# PROC106B_RST_GPIOs_I2C.net
KiCad netlist of a schematic drawn in Altium Designer
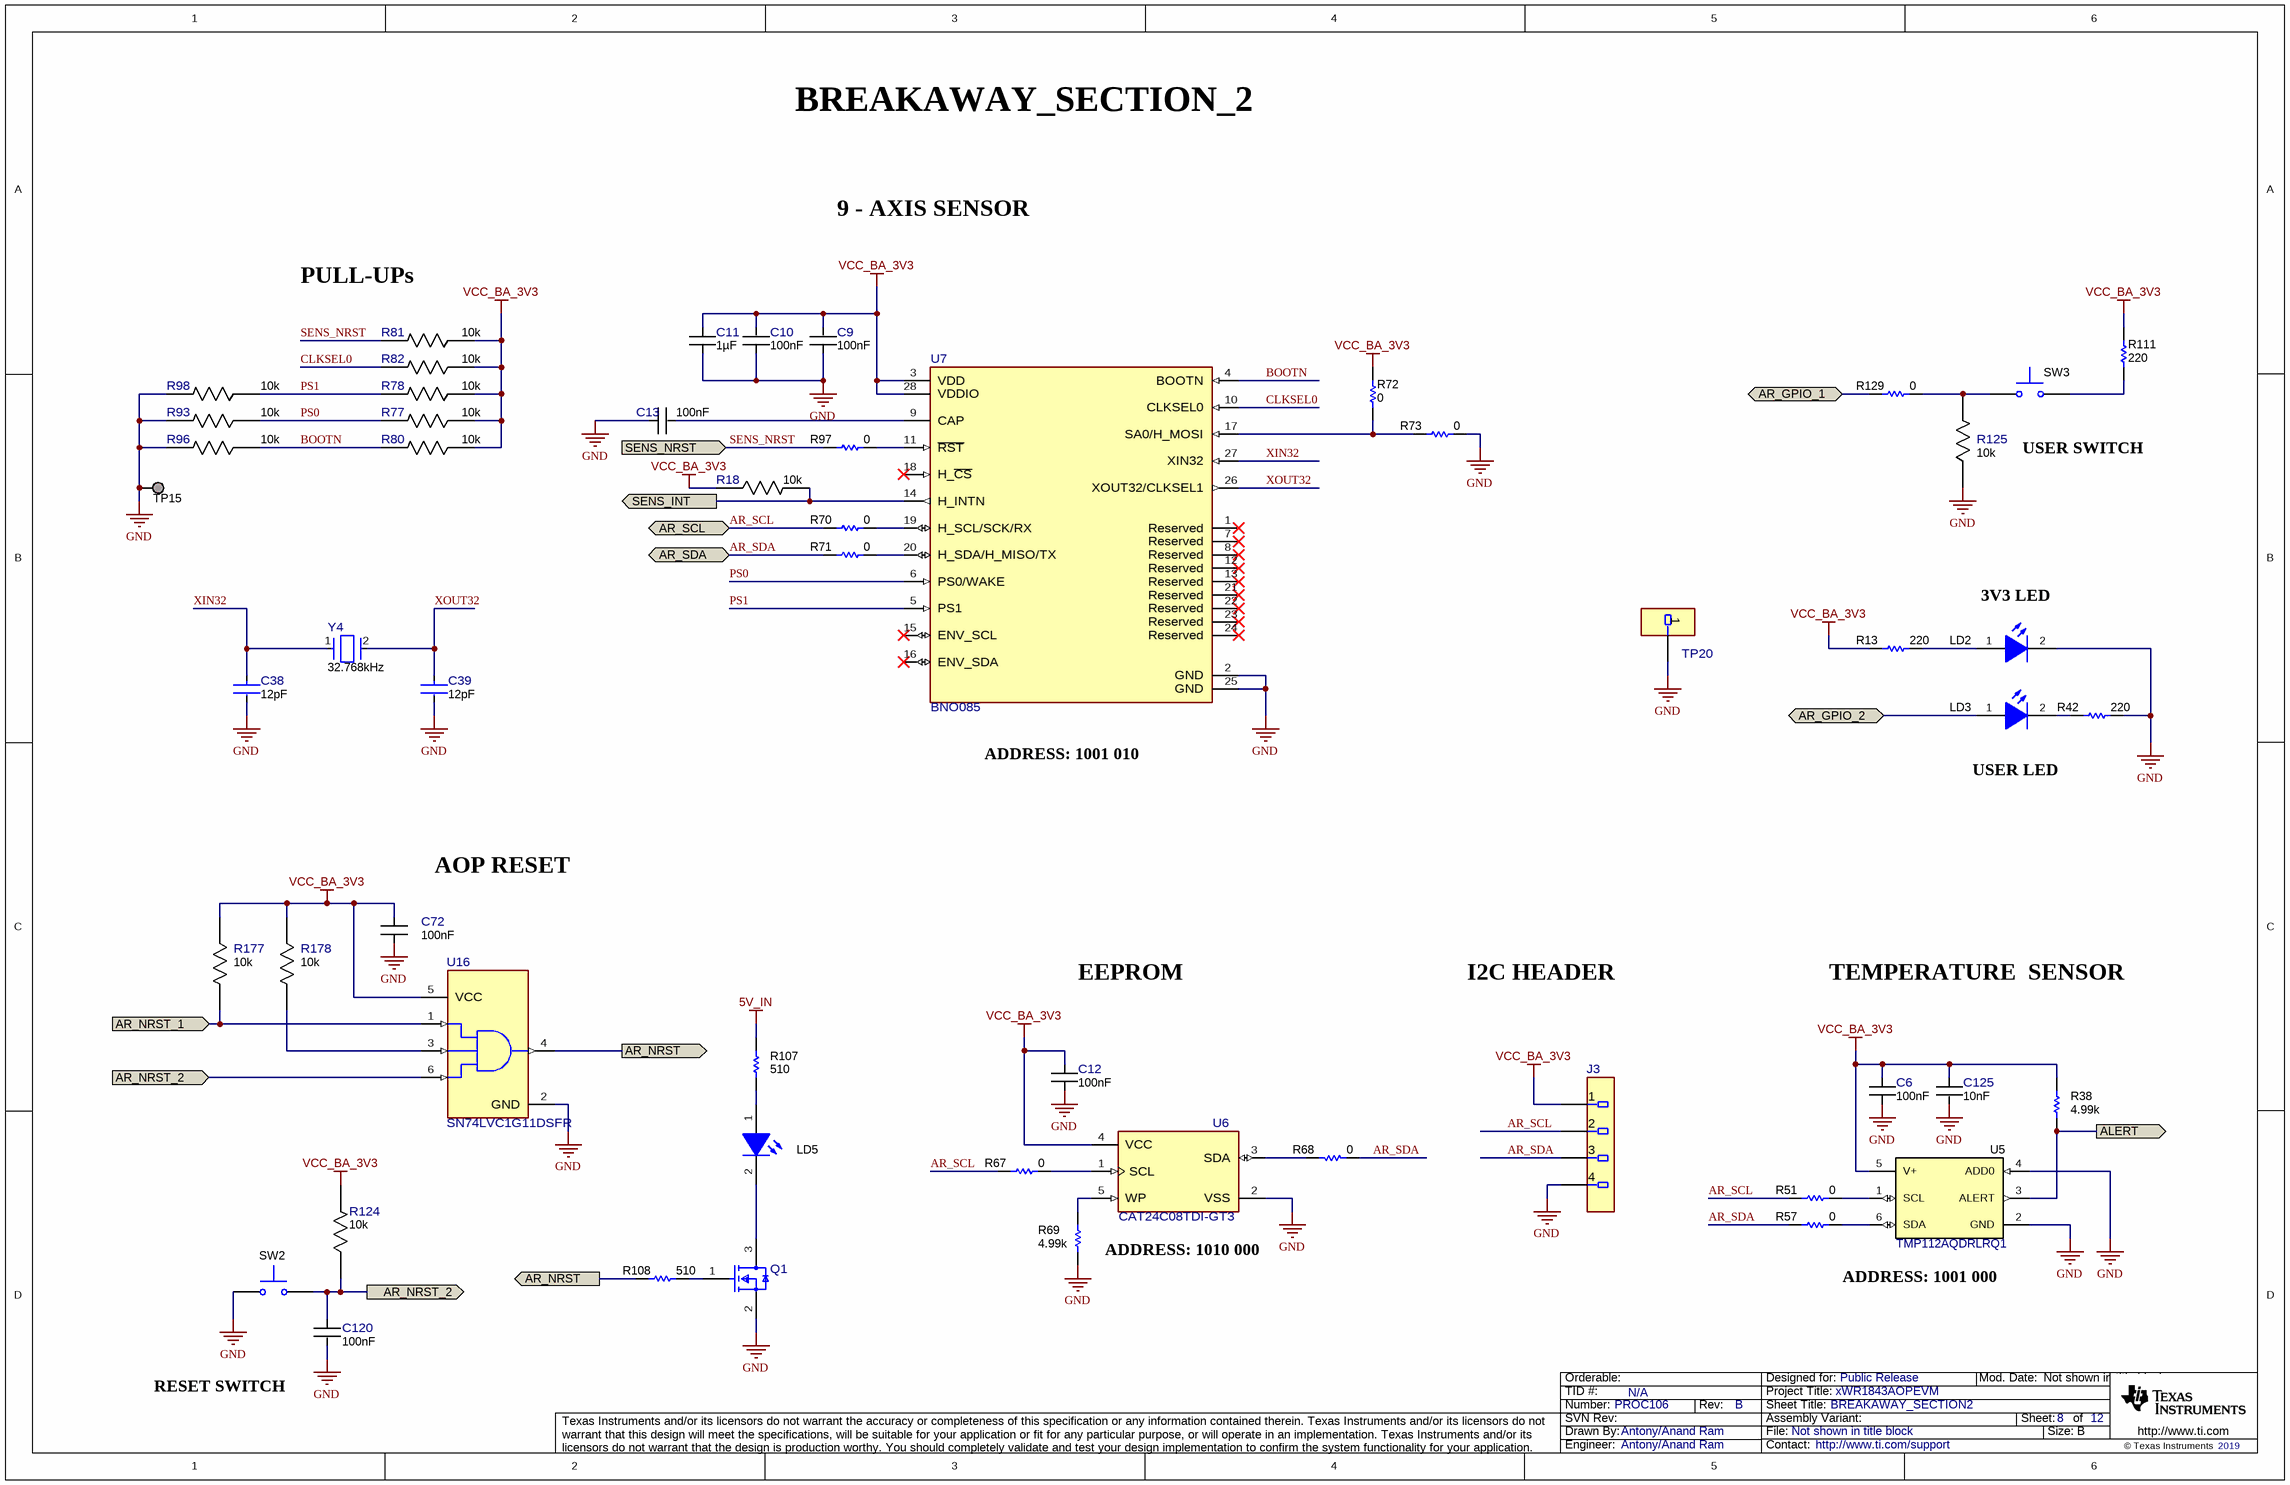
[diagram p0: PROC106B_RST_GPIOs_I2C.SchDoc]

(export (version "E")
  (design (tool "Eeschema 10.0.6"))
  (components
    (comp (ref "C6")
      (value "GRM033R6YA104KE14D")
      (footprint "FP-GRM033R6YA104KE14D_0201 (0603 Metric)-IPC_C")
      (description "Cap Ceramic 0.1uF 35V X5R 10% Pad SMD 0201 85C T/R")
      (fields (field (name "CAP_F") "100nF") (field (name "MANUFACTURER") "Murata Electronics North America"))
      (libsource (lib "Altium Vault - TI") (part "SYM-B32642B0223J"))
    )
    (comp (ref "C9")
      (value "GRM033R6YA104KE14D")
      (footprint "FP-GRM033R6YA104KE14D_0201 (0603 Metric)-IPC_C")
      (description "Cap Ceramic 0.1uF 35V X5R 10% Pad SMD 0201 85C T/R")
      (fields (field (name "CAP_F") "100nF") (field (name "MANUFACTURER") "Murata Electronics North America"))
      (libsource (lib "Altium Vault - TI") (part "SYM-B32642B0223J"))
    )
    (comp (ref "C10")
      (value "GRM033R6YA104KE14D")
      (footprint "FP-GRM033R6YA104KE14D_0201 (0603 Metric)-IPC_C")
      (description "Cap Ceramic 0.1uF 35V X5R 10% Pad SMD 0201 85C T/R")
      (fields (field (name "CAP_F") "100nF") (field (name "MANUFACTURER") "Murata Electronics North America"))
      (libsource (lib "Altium Vault - TI") (part "SYM-B32642B0223J"))
    )
    (comp (ref "C11")
      (value "CL03A105MO3NRNH")
      (footprint "FP-CL03A105MO3NRNH_0201-IPC_C")
      (description "1µF ±20% 16V Ceramic Capacitor X5R 0201")
      (fields (field (name "CAP_F") "1µF") (field (name "MANUFACTURER") "Samsung Electro-Mechanics"))
      (libsource (lib "Altium Vault - TI") (part "SYM-B32642B0223J"))
    )
    (comp (ref "C12")
      (value "GRM033R6YA104KE14D")
      (footprint "FP-GRM033R6YA104KE14D_0201 (0603 Metric)-IPC_C")
      (description "Cap Ceramic 0.1uF 35V X5R 10% Pad SMD 0201 85C T/R")
      (fields (field (name "CAP_F") "100nF") (field (name "MANUFACTURER") "Murata Electronics North America"))
      (libsource (lib "Altium Vault - TI") (part "SYM-B32642B0223J"))
    )
    (comp (ref "C13")
      (value "GRM033R6YA104KE14D")
      (footprint "FP-GRM033R6YA104KE14D_0201 (0603 Metric)-IPC_C")
      (description "Cap Ceramic 0.1uF 35V X5R 10% Pad SMD 0201 85C T/R")
      (fields (field (name "CAP_F") "100nF") (field (name "MANUFACTURER") "Murata Electronics North America"))
      (libsource (lib "Altium Vault - TI") (part "SYM-B32642B0223J"))
    )
    (comp (ref "C38")
      (value "250R05L120JV4T")
      (footprint "FP-250R05L120JV4T_0201-IPC_C")
      (description "CAP CER 12PF 25V C0G/NP0 0201")
      (fields (field (name "CAP_F") "12pF") (field (name "MANUFACTURER") "Johanson Technology Inc."))
      (libsource (lib "Altium Vault - TI") (part "SYM-CL31B335KAHVPNE"))
    )
    (comp (ref "C39")
      (value "250R05L120JV4T")
      (footprint "FP-250R05L120JV4T_0201-IPC_C")
      (description "CAP CER 12PF 25V C0G/NP0 0201")
      (fields (field (name "CAP_F") "12pF") (field (name "MANUFACTURER") "Johanson Technology Inc."))
      (libsource (lib "Altium Vault - TI") (part "SYM-CL31B335KAHVPNE"))
    )
    (comp (ref "C72")
      (value "GRM033R6YA104KE14D")
      (footprint "FP-GRM033R6YA104KE14D_0201 (0603 Metric)-IPC_C")
      (description "Cap Ceramic 0.1uF 35V X5R 10% Pad SMD 0201 85C T/R")
      (fields (field (name "CAP_F") "100nF") (field (name "MANUFACTURER") "Murata Electronics North America"))
      (libsource (lib "Altium Vault - TI") (part "SYM-B32642B0223J"))
    )
    (comp (ref "C120")
      (value "GRM033R6YA104KE14D")
      (footprint "FP-GRM033R6YA104KE14D_0201 (0603 Metric)-IPC_C")
      (description "Cap Ceramic 0.1uF 35V X5R 10% Pad SMD 0201 85C T/R")
      (fields (field (name "CAP_F") "100nF") (field (name "MANUFACTURER") "Murata Electronics North America"))
      (libsource (lib "Altium Vault - TI") (part "SYM-B32642B0223J"))
    )
    (comp (ref "C125")
      (value "CL03A103KA3NNNC")
      (footprint "FP-CL03A103KA3NNNC_0201-IPC_C")
      (description "CAP CER 10000PF 25V X5R 0201")
      (fields
        (field (name "CAP_F") "10nF")
        (field (name "MANUFACTURER") "Samsung Electro-Mechanics America, Inc")
      )
      (libsource (lib "Altium Vault - TI") (part "SYM-B32642B0223J"))
    )
    (comp (ref "J3")
      (value "M50-3930442")
      (footprint "FP-M50-3930442_HDR4-Recommended_Land_Pattern")
      (description "CONN HDR 1.27MM R/A AU 4POS")
      (fields (field (name "MANUFACTURER") "Harwin Inc."))
      (libsource (lib "Altium Vault - TI") (part "SYM-M50-3930442"))
    )
    (comp (ref "LD2")
      (value "APHHS1005CGCK")
      (footprint "APHHS1005_Green")
      (description "LED, Green, SMD")
      (fields (field (name "MANUFACTURER") "Kingbright"))
      (libsource (lib "Altium Vault - TI") (part "LED"))
    )
    (comp (ref "LD3")
      (value "APHHS1005CGCK")
      (footprint "APHHS1005_Green")
      (description "LED, Green, SMD")
      (fields (field (name "MANUFACTURER") "Kingbright"))
      (libsource (lib "Altium Vault - TI") (part "LED"))
    )
    (comp (ref "LD5")
      (value "APHHS1005CGCK")
      (footprint "APHHS1005_Green")
      (description "LED, Green, SMD")
      (fields (field (name "MANUFACTURER") "Kingbright"))
      (libsource (lib "Altium Vault - TI") (part "LED"))
    )
    (comp (ref "Q1")
      (value "BSS123-7-F")
      (footprint "FP-BSS123-7-F_SOT23-IPC_C")
      (description "MOSFET N-CH 100V 170MA SOT23-3")
      (fields (field (name "MANUFACTURER") "Diodes Incorporated"))
      (libsource (lib "Altium Vault - TI") (part "SYM-BSS123-7-F"))
    )
    (comp (ref "R13")
      (value "220")
      (footprint "0201L")
      (description "RES, 220, 5%, 0.05 W, 0201")
      (fields
        (field (name "MANUFACTURER") "Yageo America")
        (field (name "PARTNUMBER") "RC0201JR-07220RL")
        (field (name "PUBLISHER") "Texas Instruments")
      )
      (libsource (lib "Altium Vault - TI") (part "Resistor"))
    )
    (comp (ref "R18")
      (value "RR0306P-103-D")
      (footprint "FP-RR0306P-103-D_0201-IPC_C")
      (description "10 kOhms ±0.5% 0.05W, 1/20W Chip Resistor 0201 (0603 Metric)  Thin Film")
      (fields (field (name "MANUFACTURER") "Susumu") (field (name "RES_OHM") "10k"))
      (libsource (lib "Altium Vault - TI") (part "SYM-PMR18EZPJ000"))
    )
    (comp (ref "R38")
      (value "4.99k")
      (footprint "0201L")
      (description "RES, 4.99 k, 1%, 0.05 W, 0201")
      (fields
        (field (name "MANUFACTURER") "Yageo America")
        (field (name "PARTNUMBER") "RC0201FR-074K99L")
        (field (name "PUBLISHER") "Texas Instruments")
      )
      (libsource (lib "Altium Vault - TI") (part "Resistor"))
    )
    (comp (ref "R42")
      (value "220")
      (footprint "0201L")
      (description "RES, 220, 5%, 0.05 W, 0201")
      (fields
        (field (name "MANUFACTURER") "Yageo America")
        (field (name "PARTNUMBER") "RC0201JR-07220RL")
        (field (name "PUBLISHER") "Texas Instruments")
      )
      (libsource (lib "Altium Vault - TI") (part "Resistor"))
    )
    (comp (ref "R51")
      (value "RC0201JR-070RL")
      (footprint "FP-RC0201JR-070RL_0201 (0603 Metric)-MFG")
      (description "RES SMD 0 OHM JUMPER 1/20W 0201")
      (fields (field (name "MANUFACTURER") "Yageo") (field (name "RES_OHM") "0"))
      (libsource (lib "Altium Vault - TI") (part "SYM-WSR3R1500F"))
    )
    (comp (ref "R57")
      (value "RC0201JR-070RL")
      (footprint "FP-RC0201JR-070RL_0201 (0603 Metric)-MFG")
      (description "RES SMD 0 OHM JUMPER 1/20W 0201")
      (fields (field (name "MANUFACTURER") "Yageo") (field (name "RES_OHM") "0"))
      (libsource (lib "Altium Vault - TI") (part "SYM-WSR3R1500F"))
    )
    (comp (ref "R67")
      (value "RC0201JR-070RL")
      (footprint "FP-RC0201JR-070RL_0201 (0603 Metric)-MFG")
      (description "RES SMD 0 OHM JUMPER 1/20W 0201")
      (fields (field (name "MANUFACTURER") "Yageo") (field (name "RES_OHM") "0"))
      (libsource (lib "Altium Vault - TI") (part "SYM-WSR3R1500F"))
    )
    (comp (ref "R68")
      (value "RC0201JR-070RL")
      (footprint "FP-RC0201JR-070RL_0201 (0603 Metric)-MFG")
      (description "RES SMD 0 OHM JUMPER 1/20W 0201")
      (fields (field (name "MANUFACTURER") "Yageo") (field (name "RES_OHM") "0"))
      (libsource (lib "Altium Vault - TI") (part "SYM-WSR3R1500F"))
    )
    (comp (ref "R69")
      (value "4.99k")
      (footprint "0201L")
      (description "RES, 4.99 k, 1%, 0.05 W, 0201")
      (fields
        (field (name "MANUFACTURER") "Yageo America")
        (field (name "PARTNUMBER") "RC0201FR-074K99L")
        (field (name "PUBLISHER") "Texas Instruments")
      )
      (libsource (lib "Altium Vault - TI") (part "Resistor"))
    )
    (comp (ref "R70")
      (value "RC0201JR-070RL")
      (footprint "FP-RC0201JR-070RL_0201 (0603 Metric)-MFG")
      (description "RES SMD 0 OHM JUMPER 1/20W 0201")
      (fields (field (name "MANUFACTURER") "Yageo") (field (name "RES_OHM") "0"))
      (libsource (lib "Altium Vault - TI") (part "SYM-WSR3R1500F"))
    )
    (comp (ref "R71")
      (value "RC0201JR-070RL")
      (footprint "FP-RC0201JR-070RL_0201 (0603 Metric)-MFG")
      (description "RES SMD 0 OHM JUMPER 1/20W 0201")
      (fields (field (name "MANUFACTURER") "Yageo") (field (name "RES_OHM") "0"))
      (libsource (lib "Altium Vault - TI") (part "SYM-WSR3R1500F"))
    )
    (comp (ref "R72")
      (value "RC0201JR-070RL")
      (footprint "FP-RC0201JR-070RL_0201 (0603 Metric)-IPC_C")
      (description "RES SMD 0 OHM JUMPER 1/20W 0201")
      (fields (field (name "MANUFACTURER") "Yageo") (field (name "RES_OHM") "0"))
      (libsource (lib "Altium Vault - TI") (part "SYM-WSR3R1500F"))
    )
    (comp (ref "R73")
      (value "RC0201JR-070RL")
      (footprint "FP-RC0201JR-070RL_0201 (0603 Metric)-IPC_C")
      (description "RES SMD 0 OHM JUMPER 1/20W 0201")
      (fields (field (name "MANUFACTURER") "Yageo") (field (name "RES_OHM") "0"))
      (libsource (lib "Altium Vault - TI") (part "SYM-WSR3R1500F"))
    )
    (comp (ref "R77")
      (value "RR0306P-103-D")
      (footprint "FP-RR0306P-103-D_0201-IPC_C")
      (description "10 kOhms ±0.5% 0.05W, 1/20W Chip Resistor 0201 (0603 Metric)  Thin Film")
      (fields (field (name "MANUFACTURER") "Susumu") (field (name "RES_OHM") "10k"))
      (libsource (lib "Altium Vault - TI") (part "SYM-PMR18EZPJ000"))
    )
    (comp (ref "R78")
      (value "RR0306P-103-D")
      (footprint "FP-RR0306P-103-D_0201-IPC_C")
      (description "10 kOhms ±0.5% 0.05W, 1/20W Chip Resistor 0201 (0603 Metric)  Thin Film")
      (fields (field (name "MANUFACTURER") "Susumu") (field (name "RES_OHM") "10k"))
      (libsource (lib "Altium Vault - TI") (part "SYM-PMR18EZPJ000"))
    )
    (comp (ref "R80")
      (value "RR0306P-103-D")
      (footprint "FP-RR0306P-103-D_0201-IPC_C")
      (description "10 kOhms ±0.5% 0.05W, 1/20W Chip Resistor 0201 (0603 Metric)  Thin Film")
      (fields (field (name "MANUFACTURER") "Susumu") (field (name "RES_OHM") "10k"))
      (libsource (lib "Altium Vault - TI") (part "SYM-PMR18EZPJ000"))
    )
    (comp (ref "R81")
      (value "RR0306P-103-D")
      (footprint "FP-RR0306P-103-D_0201-IPC_C")
      (description "10 kOhms ±0.5% 0.05W, 1/20W Chip Resistor 0201 (0603 Metric)  Thin Film")
      (fields (field (name "MANUFACTURER") "Susumu") (field (name "RES_OHM") "10k"))
      (libsource (lib "Altium Vault - TI") (part "SYM-PMR18EZPJ000"))
    )
    (comp (ref "R82")
      (value "RR0306P-103-D")
      (footprint "FP-RR0306P-103-D_0201-IPC_C")
      (description "10 kOhms ±0.5% 0.05W, 1/20W Chip Resistor 0201 (0603 Metric)  Thin Film")
      (fields (field (name "MANUFACTURER") "Susumu") (field (name "RES_OHM") "10k"))
      (libsource (lib "Altium Vault - TI") (part "SYM-PMR18EZPJ000"))
    )
    (comp (ref "R93")
      (value "RR0306P-103-D")
      (footprint "FP-RR0306P-103-D_0201-IPC_C")
      (description "10 kOhms ±0.5% 0.05W, 1/20W Chip Resistor 0201 (0603 Metric)  Thin Film")
      (fields (field (name "MANUFACTURER") "Susumu") (field (name "RES_OHM") "10k"))
      (libsource (lib "Altium Vault - TI") (part "SYM-PMR18EZPJ000"))
    )
    (comp (ref "R96")
      (value "RR0306P-103-D")
      (footprint "FP-RR0306P-103-D_0201-IPC_C")
      (description "10 kOhms ±0.5% 0.05W, 1/20W Chip Resistor 0201 (0603 Metric)  Thin Film")
      (fields (field (name "MANUFACTURER") "Susumu") (field (name "RES_OHM") "10k"))
      (libsource (lib "Altium Vault - TI") (part "SYM-PMR18EZPJ000"))
    )
    (comp (ref "R97")
      (value "RC0201JR-070RL")
      (footprint "FP-RC0201JR-070RL_0201 (0603 Metric)-IPC_C")
      (description "RES SMD 0 OHM JUMPER 1/20W 0201")
      (fields (field (name "MANUFACTURER") "Yageo") (field (name "RES_OHM") "0"))
      (libsource (lib "Altium Vault - TI") (part "SYM-WSR3R1500F"))
    )
    (comp (ref "R98")
      (value "RR0306P-103-D")
      (footprint "FP-RR0306P-103-D_0201-IPC_C")
      (description "10 kOhms ±0.5% 0.05W, 1/20W Chip Resistor 0201 (0603 Metric)  Thin Film")
      (fields (field (name "MANUFACTURER") "Susumu") (field (name "RES_OHM") "10k"))
      (libsource (lib "Altium Vault - TI") (part "SYM-PMR18EZPJ000"))
    )
    (comp (ref "R107")
      (value "510")
      (footprint "0201L")
      (description "RES, 510, 5%, 0.05 W, 0201")
      (fields
        (field (name "MANUFACTURER") "Yageo America")
        (field (name "PARTNUMBER") "RC0201JR-07510RL")
        (field (name "PUBLISHER") "Texas Instruments")
      )
      (libsource (lib "Altium Vault - TI") (part "Resistor"))
    )
    (comp (ref "R108")
      (value "510")
      (footprint "0201L")
      (description "RES, 510, 5%, 0.05 W, 0201")
      (fields
        (field (name "MANUFACTURER") "Yageo America")
        (field (name "PARTNUMBER") "RC0201JR-07510RL")
        (field (name "PUBLISHER") "Texas Instruments")
      )
      (libsource (lib "Altium Vault - TI") (part "Resistor"))
    )
    (comp (ref "R111")
      (value "220")
      (footprint "0201L")
      (description "RES, 220, 5%, 0.05 W, 0201")
      (fields
        (field (name "MANUFACTURER") "Yageo America")
        (field (name "PARTNUMBER") "RC0201JR-07220RL")
        (field (name "PUBLISHER") "Texas Instruments")
      )
      (libsource (lib "Altium Vault - TI") (part "Resistor"))
    )
    (comp (ref "R124")
      (value "RR0306P-103-D")
      (footprint "FP-RR0306P-103-D_0201-IPC_C")
      (description "10 kOhms ±0.5% 0.05W, 1/20W Chip Resistor 0201 (0603 Metric)  Thin Film")
      (fields (field (name "MANUFACTURER") "Susumu") (field (name "RES_OHM") "10k"))
      (libsource (lib "Altium Vault - TI") (part "SYM-PMR18EZPJ000"))
    )
    (comp (ref "R125")
      (value "RR0306P-103-D")
      (footprint "FP-RR0306P-103-D_0201-IPC_C")
      (description "10 kOhms ±0.5% 0.05W, 1/20W Chip Resistor 0201 (0603 Metric)  Thin Film")
      (fields (field (name "MANUFACTURER") "Susumu") (field (name "RES_OHM") "10k"))
      (libsource (lib "Altium Vault - TI") (part "SYM-PMR18EZPJ000"))
    )
    (comp (ref "R129")
      (value "RC0201JR-070RL")
      (footprint "FP-RC0201JR-070RL_0201 (0603 Metric)-IPC_C")
      (description "RES SMD 0 OHM JUMPER 1/20W 0201")
      (fields (field (name "MANUFACTURER") "Yageo") (field (name "RES_OHM") "0"))
      (libsource (lib "Altium Vault - TI") (part "SYM-WSR3R1500F"))
    )
    (comp (ref "R177")
      (value "RR0306P-103-D")
      (footprint "FP-RR0306P-103-D_0201-IPC_C")
      (description "10 kOhms ±0.5% 0.05W, 1/20W Chip Resistor 0201 (0603 Metric)  Thin Film")
      (fields (field (name "MANUFACTURER") "Susumu") (field (name "RES_OHM") "10k"))
      (libsource (lib "Altium Vault - TI") (part "SYM-PMR18EZPJ000"))
    )
    (comp (ref "R178")
      (value "RR0306P-103-D")
      (footprint "FP-RR0306P-103-D_0201-IPC_C")
      (description "10 kOhms ±0.5% 0.05W, 1/20W Chip Resistor 0201 (0603 Metric)  Thin Film")
      (fields (field (name "MANUFACTURER") "Susumu") (field (name "RES_OHM") "10k"))
      (libsource (lib "Altium Vault - TI") (part "SYM-PMR18EZPJ000"))
    )
    (comp (ref "SW2")
      (value "B3U-1000P")
      (footprint "SW_B3U-1000P")
      (description "SWITCH TACTILE SPST-NO 0.05A 12V")
      (fields
        (field (name "MANUFACTURER") "Omron Electronic Components")
        (field (name "PUBLISHER") "Texas Instruments")
      )
      (libsource (lib "Altium Vault - TI") (part "Switch_PushButton"))
    )
    (comp (ref "SW3")
      (value "B3U-1000P")
      (footprint "SW_B3U-1000P")
      (description "SWITCH TACTILE SPST-NO 0.05A 12V")
      (fields
        (field (name "MANUFACTURER") "Omron Electronic Components")
        (field (name "PUBLISHER") "Texas Instruments")
      )
      (libsource (lib "Altium Vault - TI") (part "Switch_PushButton"))
    )
    (comp (ref "TP15")
      (value "TESTPOINT")
      (footprint "TP_25MIL-SMT")
      (description "TEST POINT.  No entry in BOM.")
      (libsource (lib "Altium Vault - TI") (part "TESTPOINT"))
    )
    (comp (ref "TP20")
      (value "4953")
      (footprint "FP-4953_HDR1-MFG")
      (description "PC Test Point, Loop Brass, Tin Plating 0.047\" (1.19mm) Hole Diameter Mounting Type")
      (fields (field (name "MANUFACTURER") "Keystone Electronics"))
      (libsource (lib "Altium Vault - TI") (part "SYM-4953"))
    )
    (comp (ref "U5")
      (value "TMP112AQDRLRQ1")
      (footprint "DRL0006A")
      (fields
        (field (name "MANUFACTURER") "Texas Instruments")
        (field (name "PUBLISHER") "Texas Instruments")
      )
      (libsource (lib "Altium Vault - TI") (part "TMP112"))
    )
    (comp (ref "U6")
      (value "CAT24C08TDI-GT3")
      (footprint "FP-CAT24C08TDI-GT3_TSOT-23-5-IPC_A")
      (description "8KB I2C SER EEPROM TSOT 23")
      (fields (field (name "MANUFACTURER") "ON Semiconductor"))
      (libsource (lib "Altium Vault - TI") (part "SYM-CAT24C08TDI-GT3"))
    )
    (comp (ref "U7")
      (value "BNO085")
      (footprint "FP-BNO085_LGA28-MFG")
      (description "IMU ACCEL/GYRO/MAG I2C 32BIT")
      (fields (field (name "MANUFACTURER") "Hillcrest Laboratories, Inc."))
      (libsource (lib "Altium Vault - TI") (part "SYM-BNO085"))
    )
    (comp (ref "U16")
      (value "SN74LVC1G11DSFR")
      (footprint "DSF0006A-MFG")
      (description "AND Gate IC 1 Channel  6-SON (1x1)")
      (fields
        (field (name "MOUSER PART NUMBER") "595-SN74LVC1G11DSFR")
        (field (name "DIGIKEY PART NUMBER") "296-30121-1-ND")
      )
      (libsource (lib "Altium Vault - TI") (part "SYM-SN74LVC1G11DSFR"))
    )
    (comp (ref "Y4")
      (value "ABS05W-32.768KHZ-D-2-T")
      (footprint "FP-ABS05W-32.768KHZ-D-2-T_XTAL_SMT_1MM6_1MM0-MFG")
      (description "CRYSTAL 32.768KHZ 4PF SMD")
      (fields (field (name "FREQUENCY_FIXED") "32.768kHz") (field (name "MANUFACTURER") "Abracon LLC"))
      (libsource (lib "Altium Vault - TI") (part "SYM-ABS05W-32.768KHZ-D-2-T"))
    )
  )
  (nets
    (net (code "1") (name "/ALERT") (class "Default")
      (node (ref "R38") (pin "1") (pinfunction "1_1") (pintype "passive"))
      (node (ref "U5") (pin "3") (pinfunction "ALERT_3") (pintype "output"))
    )
    (net (code "2") (name "/AR_GPIO_1") (class "Default")
      (node (ref "R129") (pin "2") (pinfunction "2_2") (pintype "passive"))
    )
    (net (code "3") (name "/AR_GPIO_2") (class "Default")
      (node (ref "LD3") (pin "1") (pinfunction "A_1") (pintype "passive"))
    )
    (net (code "4") (name "/AR_NRST") (class "Default")
      (node (ref "R108") (pin "1") (pinfunction "1_1") (pintype "passive"))
      (node (ref "U16") (pin "4") (pinfunction "Y_4") (pintype "output"))
    )
    (net (code "5") (name "/AR_NRST_1") (class "Default")
      (node (ref "R177") (pin "2") (pinfunction "2_2") (pintype "passive"))
      (node (ref "U16") (pin "1") (pinfunction "A_1") (pintype "input"))
    )
    (net (code "6") (name "/AR_NRST_2") (class "Default")
      (node (ref "C120") (pin "1") (pinfunction "1_1") (pintype "passive"))
      (node (ref "R124") (pin "1") (pinfunction "1_1") (pintype "passive"))
      (node (ref "SW2") (pin "1") (pinfunction "1_1") (pintype "passive"))
      (node (ref "U16") (pin "6") (pinfunction "C_6") (pintype "input"))
    )
    (net (code "7") (name "/AR_SCL") (class "Default")
      (node (ref "J3") (pin "2") (pinfunction "2_2") (pintype "passive"))
      (node (ref "R51") (pin "1") (pinfunction "1_1") (pintype "passive"))
      (node (ref "R67") (pin "1") (pinfunction "1_1") (pintype "passive"))
      (node (ref "R70") (pin "2") (pinfunction "2_2") (pintype "passive"))
    )
    (net (code "8") (name "/AR_SDA") (class "Default")
      (node (ref "J3") (pin "3") (pinfunction "3_3") (pintype "passive"))
      (node (ref "R57") (pin "1") (pinfunction "1_1") (pintype "passive"))
      (node (ref "R68") (pin "1") (pinfunction "1_1") (pintype "passive"))
      (node (ref "R71") (pin "2") (pinfunction "2_2") (pintype "passive"))
    )
    (net (code "9") (name "/BOOTN") (class "Default")
      (node (ref "R80") (pin "2") (pinfunction "2_2") (pintype "passive"))
      (node (ref "R96") (pin "1") (pinfunction "1_1") (pintype "passive"))
      (node (ref "U7") (pin "4") (pinfunction "BOOTN_4") (pintype "input"))
    )
    (net (code "10") (name "/CLKSEL0") (class "Default")
      (node (ref "R82") (pin "2") (pinfunction "2_2") (pintype "passive"))
      (node (ref "U7") (pin "10") (pinfunction "CLKSEL0_10") (pintype "input"))
    )
    (net (code "11") (name "/PS0") (class "Default")
      (node (ref "R77") (pin "2") (pinfunction "2_2") (pintype "passive"))
      (node (ref "R93") (pin "1") (pinfunction "1_1") (pintype "passive"))
      (node (ref "U7") (pin "6") (pinfunction "PS0/WAKE_6") (pintype "input"))
    )
    (net (code "12") (name "/PS1") (class "Default")
      (node (ref "R78") (pin "2") (pinfunction "2_2") (pintype "passive"))
      (node (ref "R98") (pin "1") (pinfunction "1_1") (pintype "passive"))
      (node (ref "U7") (pin "5") (pinfunction "PS1_5") (pintype "input"))
    )
    (net (code "13") (name "/SENS_INT") (class "Default")
      (node (ref "R18") (pin "2") (pinfunction "2_2") (pintype "passive"))
      (node (ref "U7") (pin "14") (pinfunction "H_INTN_14") (pintype "output"))
    )
    (net (code "14") (name "/SENS_NRST") (class "Default")
      (node (ref "R81") (pin "2") (pinfunction "2_2") (pintype "passive"))
      (node (ref "R97") (pin "2") (pinfunction "2_2") (pintype "passive"))
    )
    (net (code "15") (name "/XIN32") (class "Default")
      (node (ref "C38") (pin "1") (pinfunction "1_1") (pintype "passive"))
      (node (ref "U7") (pin "27") (pinfunction "XIN32_27") (pintype "input"))
      (node (ref "Y4") (pin "1") (pinfunction "1_1") (pintype "passive"))
    )
    (net (code "16") (name "/XOUT32") (class "Default")
      (node (ref "C39") (pin "1") (pinfunction "1_1") (pintype "passive"))
      (node (ref "U7") (pin "26") (pinfunction "XOUT32/CLKSEL1_26") (pintype "output"))
      (node (ref "Y4") (pin "2") (pinfunction "2_2") (pintype "passive"))
    )
    (net (code "17") (name "5V_IN") (class "Default")
      (node (ref "R107") (pin "1") (pinfunction "1_1") (pintype "passive"))
    )
    (net (code "18") (name "GND") (class "Default")
      (node (ref "C10") (pin "1") (pinfunction "1_1") (pintype "passive"))
      (node (ref "C11") (pin "2") (pinfunction "2_2") (pintype "passive"))
      (node (ref "C12") (pin "1") (pinfunction "1_1") (pintype "passive"))
      (node (ref "C120") (pin "2") (pinfunction "2_2") (pintype "passive"))
      (node (ref "C125") (pin "2") (pinfunction "2_2") (pintype "passive"))
      (node (ref "C13") (pin "1") (pinfunction "1_1") (pintype "passive"))
      (node (ref "C38") (pin "2") (pinfunction "2_2") (pintype "passive"))
      (node (ref "C39") (pin "2") (pinfunction "2_2") (pintype "passive"))
      (node (ref "C6") (pin "1") (pinfunction "1_1") (pintype "passive"))
      (node (ref "C72") (pin "1") (pinfunction "1_1") (pintype "passive"))
      (node (ref "C9") (pin "1") (pinfunction "1_1") (pintype "passive"))
      (node (ref "J3") (pin "4") (pinfunction "4_4") (pintype "passive"))
      (node (ref "LD2") (pin "2") (pinfunction "K_2") (pintype "passive"))
      (node (ref "Q1") (pin "2") (pinfunction "S_2") (pintype "passive"))
      (node (ref "R125") (pin "1") (pinfunction "1_1") (pintype "passive"))
      (node (ref "R42") (pin "2") (pinfunction "2_2") (pintype "passive"))
      (node (ref "R69") (pin "1") (pinfunction "1_1") (pintype "passive"))
      (node (ref "R73") (pin "1") (pinfunction "1_1") (pintype "passive"))
      (node (ref "R93") (pin "2") (pinfunction "2_2") (pintype "passive"))
      (node (ref "R96") (pin "2") (pinfunction "2_2") (pintype "passive"))
      (node (ref "R98") (pin "2") (pinfunction "2_2") (pintype "passive"))
      (node (ref "SW2") (pin "2") (pinfunction "2_2") (pintype "passive"))
      (node (ref "TP15") (pin "1") (pintype "passive"))
      (node (ref "TP20") (pin "1") (pinfunction "1_1") (pintype "passive"))
      (node (ref "U16") (pin "2") (pinfunction "GND_2") (pintype "power_in"))
      (node (ref "U5") (pin "2") (pinfunction "GND_2") (pintype "power_in"))
      (node (ref "U5") (pin "4") (pinfunction "ADD0_4") (pintype "input"))
      (node (ref "U6") (pin "2") (pinfunction "VSS_2") (pintype "power_in"))
      (node (ref "U7") (pin "2") (pinfunction "GND_2") (pintype "power_in"))
      (node (ref "U7") (pin "25") (pinfunction "GND_25") (pintype "power_in"))
    )
    (net (code "19") (name "Net-(LD2-A)") (class "Default")
      (node (ref "LD2") (pin "1") (pinfunction "A_1") (pintype "passive"))
      (node (ref "R13") (pin "2") (pinfunction "2_2") (pintype "passive"))
    )
    (net (code "20") (name "Net-(LD3-K)") (class "Default")
      (node (ref "LD3") (pin "2") (pinfunction "K_2") (pintype "passive"))
      (node (ref "R42") (pin "1") (pinfunction "1_1") (pintype "passive"))
    )
    (net (code "21") (name "Net-(LD5-A)") (class "Default")
      (node (ref "LD5") (pin "1") (pinfunction "A_1") (pintype "passive"))
      (node (ref "R107") (pin "2") (pinfunction "2_2") (pintype "passive"))
    )
    (net (code "22") (name "Net-(LD5-K)") (class "Default")
      (node (ref "LD5") (pin "2") (pinfunction "K_2") (pintype "passive"))
      (node (ref "Q1") (pin "3") (pinfunction "D_3") (pintype "passive"))
    )
    (net (code "23") (name "Net-(Q1-G)") (class "Default")
      (node (ref "Q1") (pin "1") (pinfunction "G_1") (pintype "passive"))
      (node (ref "R108") (pin "2") (pinfunction "2_2") (pintype "passive"))
    )
    (net (code "24") (name "Net-(R111-Pad1)") (class "Default")
      (node (ref "R111") (pin "1") (pinfunction "1_1") (pintype "passive"))
      (node (ref "SW3") (pin "2") (pinfunction "2_2") (pintype "passive"))
    )
    (net (code "25") (name "Net-(R125-Pad2)") (class "Default")
      (node (ref "R125") (pin "2") (pinfunction "2_2") (pintype "passive"))
      (node (ref "R129") (pin "1") (pinfunction "1_1") (pintype "passive"))
      (node (ref "SW3") (pin "1") (pinfunction "1_1") (pintype "passive"))
    )
    (net (code "26") (name "Net-(U5-SCL)") (class "Default")
      (node (ref "R51") (pin "2") (pinfunction "2_2") (pintype "passive"))
      (node (ref "U5") (pin "1") (pinfunction "SCL_1") (pintype "bidirectional"))
    )
    (net (code "27") (name "Net-(U5-SDA)") (class "Default")
      (node (ref "R57") (pin "2") (pinfunction "2_2") (pintype "passive"))
      (node (ref "U5") (pin "6") (pinfunction "SDA_6") (pintype "bidirectional"))
    )
    (net (code "28") (name "Net-(U6-SCL)") (class "Default")
      (node (ref "R67") (pin "2") (pinfunction "2_2") (pintype "passive"))
      (node (ref "U6") (pin "1") (pinfunction "SCL_1") (pintype "input"))
    )
    (net (code "29") (name "Net-(U6-SDA)") (class "Default")
      (node (ref "R68") (pin "2") (pinfunction "2_2") (pintype "passive"))
      (node (ref "U6") (pin "3") (pinfunction "SDA_3") (pintype "bidirectional"))
    )
    (net (code "30") (name "Net-(U6-WP)") (class "Default")
      (node (ref "R69") (pin "2") (pinfunction "2_2") (pintype "passive"))
      (node (ref "U6") (pin "5") (pinfunction "WP_5") (pintype "input"))
    )
    (net (code "31") (name "Net-(U7-CAP)") (class "Default")
      (node (ref "C13") (pin "2") (pinfunction "2_2") (pintype "passive"))
      (node (ref "U7") (pin "9") (pinfunction "CAP_9") (pintype "passive"))
    )
    (net (code "32") (name "Net-(U7-H_SCL{slash}SCK{slash}RX)") (class "Default")
      (node (ref "R70") (pin "1") (pinfunction "1_1") (pintype "passive"))
      (node (ref "U7") (pin "19") (pinfunction "H_SCL/SCK/RX_19") (pintype "bidirectional"))
    )
    (net (code "33") (name "Net-(U7-H_SDA{slash}H_MISO{slash}TX)") (class "Default")
      (node (ref "R71") (pin "1") (pinfunction "1_1") (pintype "passive"))
      (node (ref "U7") (pin "20") (pinfunction "H_SDA/H_MISO/TX_20") (pintype "bidirectional"))
    )
    (net (code "34") (name "Net-(U7-SA0{slash}H_MOSI)") (class "Default")
      (node (ref "R72") (pin "2") (pinfunction "2_2") (pintype "passive"))
      (node (ref "R73") (pin "2") (pinfunction "2_2") (pintype "passive"))
      (node (ref "U7") (pin "17") (pinfunction "SA0/H_MOSI_17") (pintype "input"))
    )
    (net (code "35") (name "Net-(U7-~{RST})") (class "Default")
      (node (ref "R97") (pin "1") (pinfunction "1_1") (pintype "passive"))
      (node (ref "U7") (pin "11") (pinfunction "~{RST}_11") (pintype "input"))
    )
    (net (code "36") (name "Net-(U16-B)") (class "Default")
      (node (ref "R178") (pin "2") (pinfunction "2_2") (pintype "passive"))
      (node (ref "U16") (pin "3") (pinfunction "B_3") (pintype "input"))
    )
    (net (code "37") (name "VCC_BA_3V3") (class "Default")
      (node (ref "C10") (pin "2") (pinfunction "2_2") (pintype "passive"))
      (node (ref "C11") (pin "1") (pinfunction "1_1") (pintype "passive"))
      (node (ref "C12") (pin "2") (pinfunction "2_2") (pintype "passive"))
      (node (ref "C125") (pin "1") (pinfunction "1_1") (pintype "passive"))
      (node (ref "C6") (pin "2") (pinfunction "2_2") (pintype "passive"))
      (node (ref "C72") (pin "2") (pinfunction "2_2") (pintype "passive"))
      (node (ref "C9") (pin "2") (pinfunction "2_2") (pintype "passive"))
      (node (ref "J3") (pin "1") (pinfunction "1_1") (pintype "passive"))
      (node (ref "R111") (pin "2") (pinfunction "2_2") (pintype "passive"))
      (node (ref "R124") (pin "2") (pinfunction "2_2") (pintype "passive"))
      (node (ref "R13") (pin "1") (pinfunction "1_1") (pintype "passive"))
      (node (ref "R177") (pin "1") (pinfunction "1_1") (pintype "passive"))
      (node (ref "R178") (pin "1") (pinfunction "1_1") (pintype "passive"))
      (node (ref "R18") (pin "1") (pinfunction "1_1") (pintype "passive"))
      (node (ref "R38") (pin "2") (pinfunction "2_2") (pintype "passive"))
      (node (ref "R72") (pin "1") (pinfunction "1_1") (pintype "passive"))
      (node (ref "R77") (pin "1") (pinfunction "1_1") (pintype "passive"))
      (node (ref "R78") (pin "1") (pinfunction "1_1") (pintype "passive"))
      (node (ref "R80") (pin "1") (pinfunction "1_1") (pintype "passive"))
      (node (ref "R81") (pin "1") (pinfunction "1_1") (pintype "passive"))
      (node (ref "R82") (pin "1") (pinfunction "1_1") (pintype "passive"))
      (node (ref "U16") (pin "5") (pinfunction "VCC_5") (pintype "power_in"))
      (node (ref "U5") (pin "5") (pinfunction "V+_5") (pintype "power_in"))
      (node (ref "U6") (pin "4") (pinfunction "VCC_4") (pintype "power_in"))
      (node (ref "U7") (pin "28") (pinfunction "VDDIO_28") (pintype "power_in"))
      (node (ref "U7") (pin "3") (pinfunction "VDD_3") (pintype "power_in"))
    )
    (net (code "38") (name "unconnected-(U7-ENV_SCL-Pad15)") (class "Default")
      (node (ref "U7") (pin "15") (pinfunction "ENV_SCL_15") (pintype "bidirectional+no_connect"))
    )
    (net (code "39") (name "unconnected-(U7-ENV_SDA-Pad16)") (class "Default")
      (node (ref "U7") (pin "16") (pinfunction "ENV_SDA_16") (pintype "bidirectional+no_connect"))
    )
    (net (code "40") (name "unconnected-(U7-H_~{CS}-Pad18)") (class "Default")
      (node (ref "U7") (pin "18") (pinfunction "H_~{CS}_18") (pintype "input+no_connect"))
    )
    (net (code "41") (name "unconnected-(U7-Reserved-Pad1)") (class "Default")
      (node (ref "U7") (pin "1") (pinfunction "Reserved_1") (pintype "passive+no_connect"))
    )
    (net (code "42") (name "unconnected-(U7-Reserved-Pad7)") (class "Default")
      (node (ref "U7") (pin "7") (pinfunction "Reserved_7") (pintype "passive+no_connect"))
    )
    (net (code "43") (name "unconnected-(U7-Reserved-Pad8)") (class "Default")
      (node (ref "U7") (pin "8") (pinfunction "Reserved_8") (pintype "passive+no_connect"))
    )
    (net (code "44") (name "unconnected-(U7-Reserved-Pad12)") (class "Default")
      (node (ref "U7") (pin "12") (pinfunction "Reserved_12") (pintype "passive+no_connect"))
    )
    (net (code "45") (name "unconnected-(U7-Reserved-Pad13)") (class "Default")
      (node (ref "U7") (pin "13") (pinfunction "Reserved_13") (pintype "passive+no_connect"))
    )
    (net (code "46") (name "unconnected-(U7-Reserved-Pad21)") (class "Default")
      (node (ref "U7") (pin "21") (pinfunction "Reserved_21") (pintype "passive+no_connect"))
    )
    (net (code "47") (name "unconnected-(U7-Reserved-Pad22)") (class "Default")
      (node (ref "U7") (pin "22") (pinfunction "Reserved_22") (pintype "passive+no_connect"))
    )
    (net (code "48") (name "unconnected-(U7-Reserved-Pad23)") (class "Default")
      (node (ref "U7") (pin "23") (pinfunction "Reserved_23") (pintype "passive+no_connect"))
    )
    (net (code "49") (name "unconnected-(U7-Reserved-Pad24)") (class "Default")
      (node (ref "U7") (pin "24") (pinfunction "Reserved_24") (pintype "passive+no_connect"))
    )
  )
)
